# BaseStation_R1_1.net
KiCad netlist of a schematic drawn in EAGLE
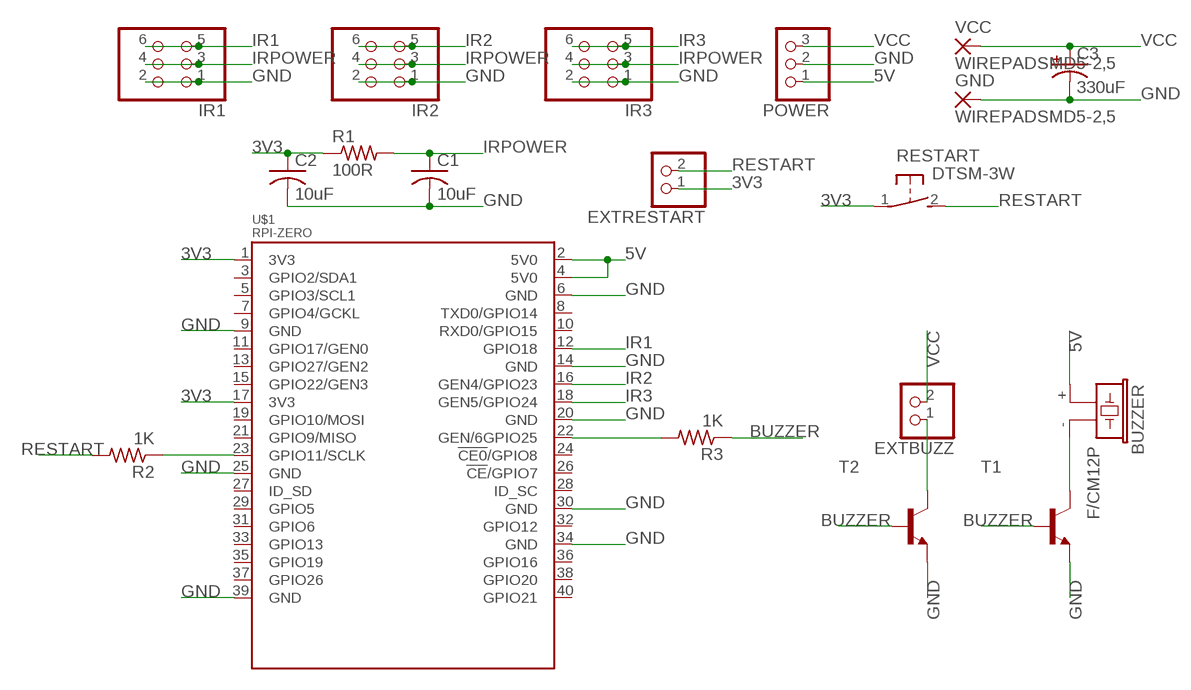
[diagram p0: schematic, sheet 1]

(export (version "E")
  (design (tool "Eeschema 10.0.6"))
  (components
    (comp (ref "BUZZER")
      (value "F/CM12P")
      (footprint "eagle-import:F_CM12P")
      (libsource (lib "eagle-import") (part "F/CM12P"))
    )
    (comp (ref "C1")
      (value "10uF")
      (footprint "eagle-import:C1206K")
      (libsource (lib "eagle-import") (part "C-USC1206K"))
    )
    (comp (ref "C2")
      (value "10uF")
      (footprint "eagle-import:C1206K")
      (libsource (lib "eagle-import") (part "C-USC1206K"))
    )
    (comp (ref "C3")
      (value "330uF")
      (footprint "eagle-import:E3,5-8")
      (libsource (lib "eagle-import") (part "CPOL-USE3.5-8"))
    )
    (comp (ref "EXTBUZZ")
      (value "PINHD-1X2")
      (footprint "eagle-import:1X02")
      (libsource (lib "eagle-import") (part "PINHD-1X2"))
    )
    (comp (ref "EXTRESTART")
      (value "PINHD-1X2")
      (footprint "eagle-import:1X02")
      (libsource (lib "eagle-import") (part "PINHD-1X2"))
    )
    (comp (ref "GND")
      (value "WIREPADSMD5-2,5")
      (footprint "eagle-import:5-2,5")
      (libsource (lib "eagle-import") (part "WIREPADSMD5-2,5"))
    )
    (comp (ref "IR1")
      (value "PINHD-2X3")
      (footprint "eagle-import:2X03")
      (libsource (lib "eagle-import") (part "PINHD-2X3"))
    )
    (comp (ref "IR2")
      (value "PINHD-2X3")
      (footprint "eagle-import:2X03")
      (libsource (lib "eagle-import") (part "PINHD-2X3"))
    )
    (comp (ref "IR3")
      (value "PINHD-2X3")
      (footprint "eagle-import:2X03")
      (libsource (lib "eagle-import") (part "PINHD-2X3"))
    )
    (comp (ref "POWER")
      (value "PINHD-1X3")
      (footprint "eagle-import:1X03")
      (libsource (lib "eagle-import") (part "PINHD-1X3"))
    )
    (comp (ref "R1")
      (value "100R")
      (footprint "eagle-import:R1206W")
      (libsource (lib "eagle-import") (part "R-US_R1206W"))
    )
    (comp (ref "R2")
      (value "1K")
      (footprint "eagle-import:R1206W")
      (libsource (lib "eagle-import") (part "R-US_R1206W"))
    )
    (comp (ref "R3")
      (value "1K")
      (footprint "eagle-import:R1206W")
      (libsource (lib "eagle-import") (part "R-US_R1206W"))
    )
    (comp (ref "RESTART")
      (value "DTSM-3W")
      (footprint "eagle-import:DTSM-3W")
      (libsource (lib "eagle-import") (part "DTSM-3W"))
    )
    (comp (ref "T1")
      (value "MMBT2222ALT1-NPN-SOT23-BEC")
      (footprint "eagle-import:SOT23-BEC")
      (libsource (lib "eagle-import") (part "-NPN-SOT23-BECMMBT2222ALT1"))
    )
    (comp (ref "T2")
      (value "MMBT2222ALT1-NPN-SOT23-BEC")
      (footprint "eagle-import:SOT23-BEC")
      (libsource (lib "eagle-import") (part "-NPN-SOT23-BECMMBT2222ALT1"))
    )
    (comp (ref "U$1")
      (value "RPI-ZERO")
      (footprint "eagle-import:RASPBERRYPI_BASTELSTUBE_V13_RASPI_BOARD_B+_FULL")
      (libsource (lib "eagle-import") (part "RPI-ZERO"))
    )
    (comp (ref "VCC")
      (value "WIREPADSMD5-2,5")
      (footprint "eagle-import:5-2,5")
      (libsource (lib "eagle-import") (part "WIREPADSMD5-2,5"))
    )
  )
  (nets
    (net (code "1") (name "/3V3") (class "Default")
      (node (ref "C2") (pin "1") (pinfunction "1_1") (pintype "passive"))
      (node (ref "EXTRESTART") (pin "1") (pinfunction "1_1") (pintype "passive"))
      (node (ref "R1") (pin "1") (pinfunction "1_1") (pintype "passive"))
      (node (ref "RESTART") (pin "1") (pinfunction "1_1") (pintype "passive"))
      (node (ref "U$1") (pin "1") (pinfunction "3V3_1") (pintype "power_in"))
      (node (ref "U$1") (pin "17") (pinfunction "3V3_17") (pintype "power_in"))
    )
    (net (code "2") (name "/5V") (class "Default")
      (node (ref "BUZZER") (pin "+") (pinfunction "1_+") (pintype "passive"))
      (node (ref "POWER") (pin "1") (pinfunction "1_1") (pintype "passive"))
      (node (ref "U$1") (pin "2") (pinfunction "5V0_2") (pintype "power_in"))
      (node (ref "U$1") (pin "4") (pinfunction "5V0_4") (pintype "power_in"))
    )
    (net (code "3") (name "/BUZZER") (class "Default")
      (node (ref "R3") (pin "1") (pinfunction "1_1") (pintype "passive"))
      (node (ref "T1") (pin "B") (pinfunction "B_B") (pintype "passive"))
      (node (ref "T2") (pin "B") (pinfunction "B_B") (pintype "passive"))
    )
    (net (code "4") (name "/GND") (class "Default")
      (node (ref "C1") (pin "2") (pinfunction "2_2") (pintype "passive"))
      (node (ref "C2") (pin "2") (pinfunction "2_2") (pintype "passive"))
      (node (ref "C3") (pin "-") (pinfunction "-_-") (pintype "passive"))
      (node (ref "GND") (pin "1") (pinfunction "P_1") (pintype "passive"))
      (node (ref "IR1") (pin "1") (pinfunction "1_1") (pintype "passive"))
      (node (ref "IR1") (pin "2") (pinfunction "2_2") (pintype "passive"))
      (node (ref "IR2") (pin "1") (pinfunction "1_1") (pintype "passive"))
      (node (ref "IR2") (pin "2") (pinfunction "2_2") (pintype "passive"))
      (node (ref "IR3") (pin "1") (pinfunction "1_1") (pintype "passive"))
      (node (ref "IR3") (pin "2") (pinfunction "2_2") (pintype "passive"))
      (node (ref "POWER") (pin "2") (pinfunction "2_2") (pintype "passive"))
      (node (ref "T1") (pin "E") (pinfunction "E_E") (pintype "passive"))
      (node (ref "T2") (pin "E") (pinfunction "E_E") (pintype "passive"))
      (node (ref "U$1") (pin "14") (pinfunction "GND_14") (pintype "power_in"))
      (node (ref "U$1") (pin "20") (pinfunction "GND_20") (pintype "power_in"))
      (node (ref "U$1") (pin "25") (pinfunction "GND_25") (pintype "power_in"))
      (node (ref "U$1") (pin "30") (pinfunction "GND_30") (pintype "power_in"))
      (node (ref "U$1") (pin "34") (pinfunction "GND_34") (pintype "power_in"))
      (node (ref "U$1") (pin "39") (pinfunction "GND_39") (pintype "power_in"))
      (node (ref "U$1") (pin "6") (pinfunction "GND_6") (pintype "power_in"))
      (node (ref "U$1") (pin "9") (pinfunction "GND_9") (pintype "power_in"))
    )
    (net (code "5") (name "/IR1") (class "Default")
      (node (ref "IR1") (pin "5") (pinfunction "5_5") (pintype "passive"))
      (node (ref "IR1") (pin "6") (pinfunction "6_6") (pintype "passive"))
      (node (ref "U$1") (pin "12") (pinfunction "GPIO18_12") (pintype "bidirectional"))
    )
    (net (code "6") (name "/IR2") (class "Default")
      (node (ref "IR2") (pin "5") (pinfunction "5_5") (pintype "passive"))
      (node (ref "IR2") (pin "6") (pinfunction "6_6") (pintype "passive"))
      (node (ref "U$1") (pin "16") (pinfunction "GEN4/GPIO23_16") (pintype "bidirectional"))
    )
    (net (code "7") (name "/IR3") (class "Default")
      (node (ref "IR3") (pin "5") (pinfunction "5_5") (pintype "passive"))
      (node (ref "IR3") (pin "6") (pinfunction "6_6") (pintype "passive"))
      (node (ref "U$1") (pin "18") (pinfunction "GEN5/GPIO24_18") (pintype "bidirectional"))
    )
    (net (code "8") (name "/IRPOWER") (class "Default")
      (node (ref "C1") (pin "1") (pinfunction "1_1") (pintype "passive"))
      (node (ref "IR1") (pin "3") (pinfunction "3_3") (pintype "passive"))
      (node (ref "IR1") (pin "4") (pinfunction "4_4") (pintype "passive"))
      (node (ref "IR2") (pin "3") (pinfunction "3_3") (pintype "passive"))
      (node (ref "IR2") (pin "4") (pinfunction "4_4") (pintype "passive"))
      (node (ref "IR3") (pin "3") (pinfunction "3_3") (pintype "passive"))
      (node (ref "IR3") (pin "4") (pinfunction "4_4") (pintype "passive"))
      (node (ref "R1") (pin "2") (pinfunction "2_2") (pintype "passive"))
    )
    (net (code "9") (name "/RESTART") (class "Default")
      (node (ref "EXTRESTART") (pin "2") (pinfunction "2_2") (pintype "passive"))
      (node (ref "R2") (pin "2") (pinfunction "2_2") (pintype "passive"))
      (node (ref "RESTART") (pin "2") (pinfunction "2_2") (pintype "passive"))
    )
    (net (code "10") (name "/VCC") (class "Default")
      (node (ref "C3") (pin "+") (pinfunction "+_+") (pintype "passive"))
      (node (ref "EXTBUZZ") (pin "2") (pinfunction "2_2") (pintype "passive"))
      (node (ref "POWER") (pin "3") (pinfunction "3_3") (pintype "passive"))
      (node (ref "VCC") (pin "1") (pinfunction "P_1") (pintype "passive"))
    )
    (net (code "11") (name "Net-(BUZZER-2)") (class "Default")
      (node (ref "BUZZER") (pin "-") (pinfunction "2_-") (pintype "passive"))
      (node (ref "T1") (pin "C") (pinfunction "C_C") (pintype "passive"))
    )
    (net (code "12") (name "Net-(EXTBUZZ-Pad1)") (class "Default")
      (node (ref "EXTBUZZ") (pin "1") (pinfunction "1_1") (pintype "passive"))
      (node (ref "T2") (pin "C") (pinfunction "C_C") (pintype "passive"))
    )
    (net (code "13") (name "Net-(U$1-GEN{slash}6GPIO25)") (class "Default")
      (node (ref "R3") (pin "2") (pinfunction "2_2") (pintype "passive"))
      (node (ref "U$1") (pin "22") (pinfunction "GEN/6GPIO25_22") (pintype "bidirectional"))
    )
    (net (code "14") (name "Net-(U$1-GPIO11{slash}SCLK)") (class "Default")
      (node (ref "R2") (pin "1") (pinfunction "1_1") (pintype "passive"))
      (node (ref "U$1") (pin "23") (pinfunction "GPIO11/SCLK_23") (pintype "bidirectional"))
    )
    (net (code "15") (name "unconnected-(U$1-GPIO2{slash}SDA1-Pad3)") (class "Default")
      (node (ref "U$1") (pin "3") (pinfunction "GPIO2/SDA1_3") (pintype "bidirectional"))
    )
    (net (code "16") (name "unconnected-(U$1-GPIO3{slash}SCL1-Pad5)") (class "Default")
      (node (ref "U$1") (pin "5") (pinfunction "GPIO3/SCL1_5") (pintype "bidirectional"))
    )
    (net (code "17") (name "unconnected-(U$1-GPIO4{slash}GCKL-Pad7)") (class "Default")
      (node (ref "U$1") (pin "7") (pinfunction "GPIO4/GCKL_7") (pintype "bidirectional"))
    )
    (net (code "18") (name "unconnected-(U$1-GPIO5-Pad29)") (class "Default")
      (node (ref "U$1") (pin "29") (pinfunction "GPIO5_29") (pintype "bidirectional"))
    )
    (net (code "19") (name "unconnected-(U$1-GPIO6-Pad31)") (class "Default")
      (node (ref "U$1") (pin "31") (pinfunction "GPIO6_31") (pintype "bidirectional"))
    )
    (net (code "20") (name "unconnected-(U$1-GPIO9{slash}MISO-Pad21)") (class "Default")
      (node (ref "U$1") (pin "21") (pinfunction "GPIO9/MISO_21") (pintype "bidirectional"))
    )
    (net (code "21") (name "unconnected-(U$1-GPIO10{slash}MOSI-Pad19)") (class "Default")
      (node (ref "U$1") (pin "19") (pinfunction "GPIO10/MOSI_19") (pintype "bidirectional"))
    )
    (net (code "22") (name "unconnected-(U$1-GPIO12-Pad32)") (class "Default")
      (node (ref "U$1") (pin "32") (pinfunction "GPIO12_32") (pintype "bidirectional"))
    )
    (net (code "23") (name "unconnected-(U$1-GPIO13-Pad33)") (class "Default")
      (node (ref "U$1") (pin "33") (pinfunction "GPIO13_33") (pintype "bidirectional"))
    )
    (net (code "24") (name "unconnected-(U$1-GPIO16-Pad36)") (class "Default")
      (node (ref "U$1") (pin "36") (pinfunction "GPIO16_36") (pintype "bidirectional"))
    )
    (net (code "25") (name "unconnected-(U$1-GPIO17{slash}GEN0-Pad11)") (class "Default")
      (node (ref "U$1") (pin "11") (pinfunction "GPIO17/GEN0_11") (pintype "bidirectional"))
    )
    (net (code "26") (name "unconnected-(U$1-GPIO19-Pad35)") (class "Default")
      (node (ref "U$1") (pin "35") (pinfunction "GPIO19_35") (pintype "bidirectional"))
    )
    (net (code "27") (name "unconnected-(U$1-GPIO20-Pad38)") (class "Default")
      (node (ref "U$1") (pin "38") (pinfunction "GPIO20_38") (pintype "bidirectional"))
    )
    (net (code "28") (name "unconnected-(U$1-GPIO21-Pad40)") (class "Default")
      (node (ref "U$1") (pin "40") (pinfunction "GPIO21_40") (pintype "bidirectional"))
    )
    (net (code "29") (name "unconnected-(U$1-GPIO22{slash}GEN3-Pad15)") (class "Default")
      (node (ref "U$1") (pin "15") (pinfunction "GPIO22/GEN3_15") (pintype "bidirectional"))
    )
    (net (code "30") (name "unconnected-(U$1-GPIO26-Pad37)") (class "Default")
      (node (ref "U$1") (pin "37") (pinfunction "GPIO26_37") (pintype "bidirectional"))
    )
    (net (code "31") (name "unconnected-(U$1-GPIO27{slash}GEN2-Pad13)") (class "Default")
      (node (ref "U$1") (pin "13") (pinfunction "GPIO27/GEN2_13") (pintype "bidirectional"))
    )
    (net (code "32") (name "unconnected-(U$1-ID_SC-Pad28)") (class "Default")
      (node (ref "U$1") (pin "28") (pinfunction "ID_SC_28") (pintype "bidirectional"))
    )
    (net (code "33") (name "unconnected-(U$1-ID_SD-Pad27)") (class "Default")
      (node (ref "U$1") (pin "27") (pinfunction "ID_SD_27") (pintype "bidirectional"))
    )
    (net (code "34") (name "unconnected-(U$1-RXD0{slash}GPIO15-Pad10)") (class "Default")
      (node (ref "U$1") (pin "10") (pinfunction "RXD0/GPIO15_10") (pintype "bidirectional"))
    )
    (net (code "35") (name "unconnected-(U$1-TXD0{slash}GPIO14-Pad8)") (class "Default")
      (node (ref "U$1") (pin "8") (pinfunction "TXD0/GPIO14_8") (pintype "bidirectional"))
    )
    (net (code "36") (name "unconnected-(U$1-~{CE0}{slash}GPIO8-Pad24)") (class "Default")
      (node (ref "U$1") (pin "24") (pinfunction "~{CE0}/GPIO8_24") (pintype "bidirectional"))
    )
    (net (code "37") (name "unconnected-(U$1-~{CE}{slash}GPIO7-Pad26)") (class "Default")
      (node (ref "U$1") (pin "26") (pinfunction "~{CE}/GPIO7_26") (pintype "bidirectional"))
    )
  )
)
